# Power_Supply.net
KiCad netlist of a schematic drawn in Altium Designer
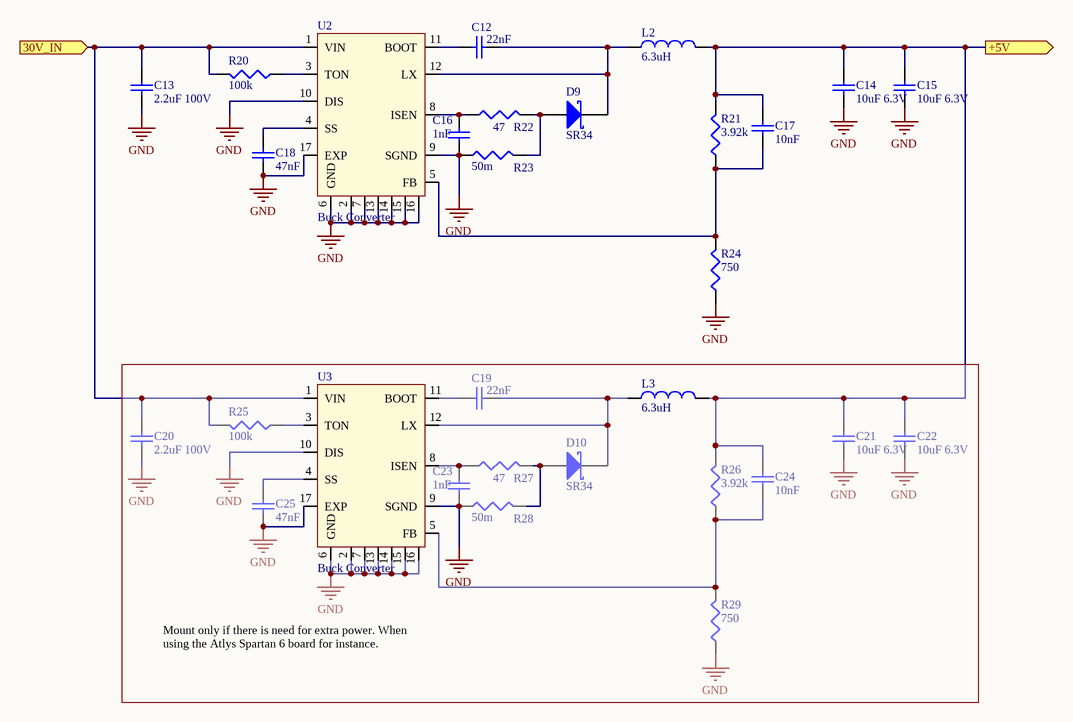
[diagram p0: Power Supply.SchDoc]

(export (version "E")
  (design (tool "Eeschema 10.0.6"))
  (components
    (comp (ref "C12")
      (value "22nF")
      (footprint "6-0805_N")
      (description "Capacitor (Semiconductor SIM Model)")
      (fields (field (name "Comment") "Cap Semi") (field (name "PUBLISHER") "Altium Limited"))
      (libsource (lib "Miscellaneous Devices") (part "Cap Semi"))
    )
    (comp (ref "C13")
      (value "2.2uF 100V")
      (footprint "C1210")
      (description "Capacitor (Semiconductor SIM Model)")
      (fields (field (name "Comment") "Cap Semi") (field (name "PUBLISHER") "Altium Limited"))
      (libsource (lib "Miscellaneous Devices") (part "Cap Semi"))
    )
    (comp (ref "C14")
      (value "10uF 6.3V")
      (footprint "6-0805_N")
      (description "Capacitor (Semiconductor SIM Model)")
      (fields (field (name "Comment") "Cap Semi") (field (name "PUBLISHER") "Altium Limited"))
      (libsource (lib "Miscellaneous Devices") (part "Cap Semi"))
    )
    (comp (ref "C15")
      (value "10uF 6.3V")
      (footprint "6-0805_N")
      (description "Capacitor (Semiconductor SIM Model)")
      (fields (field (name "Comment") "Cap Semi") (field (name "PUBLISHER") "Altium Limited"))
      (libsource (lib "Miscellaneous Devices") (part "Cap Semi"))
    )
    (comp (ref "C16")
      (value "1nF")
      (footprint "6-0805_N")
      (description "Capacitor (Semiconductor SIM Model)")
      (fields (field (name "Comment") "Cap Semi") (field (name "PUBLISHER") "Altium Limited"))
      (libsource (lib "Miscellaneous Devices") (part "Cap Semi"))
    )
    (comp (ref "C17")
      (value "10nF")
      (footprint "6-0805_N")
      (description "Capacitor (Semiconductor SIM Model)")
      (fields (field (name "Comment") "Cap Semi") (field (name "PUBLISHER") "Altium Limited"))
      (libsource (lib "Miscellaneous Devices") (part "Cap Semi"))
    )
    (comp (ref "C18")
      (value "47nF")
      (footprint "6-0805_N")
      (description "Capacitor (Semiconductor SIM Model)")
      (fields (field (name "Comment") "Cap Semi") (field (name "PUBLISHER") "Altium Limited"))
      (libsource (lib "Miscellaneous Devices") (part "Cap Semi"))
    )
    (comp (ref "C19")
      (value "22nF")
      (footprint "6-0805_N")
      (description "Capacitor (Semiconductor SIM Model)")
      (fields (field (name "Comment") "Cap Semi") (field (name "PUBLISHER") "Altium Limited"))
      (libsource (lib "Miscellaneous Devices") (part "Cap Semi"))
    )
    (comp (ref "C20")
      (value "2.2uF 100V")
      (footprint "C1210")
      (description "Capacitor (Semiconductor SIM Model)")
      (fields (field (name "Comment") "Cap Semi") (field (name "PUBLISHER") "Altium Limited"))
      (libsource (lib "Miscellaneous Devices") (part "Cap Semi"))
    )
    (comp (ref "C21")
      (value "10uF 6.3V")
      (footprint "6-0805_N")
      (description "Capacitor (Semiconductor SIM Model)")
      (fields (field (name "Comment") "Cap Semi") (field (name "PUBLISHER") "Altium Limited"))
      (libsource (lib "Miscellaneous Devices") (part "Cap Semi"))
    )
    (comp (ref "C22")
      (value "10uF 6.3V")
      (footprint "6-0805_N")
      (description "Capacitor (Semiconductor SIM Model)")
      (fields (field (name "Comment") "Cap Semi") (field (name "PUBLISHER") "Altium Limited"))
      (libsource (lib "Miscellaneous Devices") (part "Cap Semi"))
    )
    (comp (ref "C23")
      (value "1nF")
      (footprint "6-0805_N")
      (description "Capacitor (Semiconductor SIM Model)")
      (fields (field (name "Comment") "Cap Semi") (field (name "PUBLISHER") "Altium Limited"))
      (libsource (lib "Miscellaneous Devices") (part "Cap Semi"))
    )
    (comp (ref "C24")
      (value "10nF")
      (footprint "6-0805_N")
      (description "Capacitor (Semiconductor SIM Model)")
      (fields (field (name "Comment") "Cap Semi") (field (name "PUBLISHER") "Altium Limited"))
      (libsource (lib "Miscellaneous Devices") (part "Cap Semi"))
    )
    (comp (ref "C25")
      (value "47nF")
      (footprint "6-0805_N")
      (description "Capacitor (Semiconductor SIM Model)")
      (fields (field (name "Comment") "Cap Semi") (field (name "PUBLISHER") "Altium Limited"))
      (libsource (lib "Miscellaneous Devices") (part "Cap Semi"))
    )
    (comp (ref "D9")
      (value "SR34")
      (footprint "CD4532-1812")
      (description "Schottky Diode")
      (fields (field (name "PUBLISHER") "Altium Limited"))
      (libsource (lib "Miscellaneous Devices") (part "D Schottky"))
    )
    (comp (ref "D10")
      (value "SR34")
      (footprint "CD4532-1812")
      (description "Schottky Diode")
      (fields (field (name "PUBLISHER") "Altium Limited"))
      (libsource (lib "Miscellaneous Devices") (part "D Schottky"))
    )
    (comp (ref "L2")
      (value "6.3uH")
      (footprint "WE_74477006")
      (description "Header, 3-Pin")
      (fields (field (name "PUBLISHER") "Altium Limited"))
      (libsource (lib "new_library") (part "Inductor"))
    )
    (comp (ref "L3")
      (value "6.3uH")
      (footprint "WE_74477006")
      (description "Header, 3-Pin")
      (fields (field (name "PUBLISHER") "Altium Limited"))
      (libsource (lib "new_library") (part "Inductor"))
    )
    (comp (ref "R20")
      (value "100k")
      (footprint "6-0805_L")
      (description "Resistor")
      (fields (field (name "Comment") "Res3") (field (name "PUBLISHER") "Altium Limited"))
      (libsource (lib "Miscellaneous Devices") (part "Res3"))
    )
    (comp (ref "R21")
      (value "3.92k")
      (footprint "6-0805_L")
      (description "Resistor")
      (fields (field (name "Comment") "Res3") (field (name "PUBLISHER") "Altium Limited"))
      (libsource (lib "Miscellaneous Devices") (part "Res3"))
    )
    (comp (ref "R22")
      (value "47")
      (footprint "6-0805_L")
      (description "Resistor")
      (fields (field (name "Comment") "Res3") (field (name "PUBLISHER") "Altium Limited"))
      (libsource (lib "Miscellaneous Devices") (part "Res3"))
    )
    (comp (ref "R23")
      (value "50m")
      (footprint "6-0805_L")
      (description "Resistor")
      (fields (field (name "Comment") "Res3") (field (name "PUBLISHER") "Altium Limited"))
      (libsource (lib "Miscellaneous Devices") (part "Res3"))
    )
    (comp (ref "R24")
      (value "750")
      (footprint "6-0805_L")
      (description "Resistor")
      (fields (field (name "Comment") "Res3") (field (name "PUBLISHER") "Altium Limited"))
      (libsource (lib "Miscellaneous Devices") (part "Res3"))
    )
    (comp (ref "R25")
      (value "100k")
      (footprint "6-0805_L")
      (description "Resistor")
      (fields (field (name "Comment") "Res3") (field (name "PUBLISHER") "Altium Limited"))
      (libsource (lib "Miscellaneous Devices") (part "Res3"))
    )
    (comp (ref "R26")
      (value "3.92k")
      (footprint "6-0805_L")
      (description "Resistor")
      (fields (field (name "Comment") "Res3") (field (name "PUBLISHER") "Altium Limited"))
      (libsource (lib "Miscellaneous Devices") (part "Res3"))
    )
    (comp (ref "R27")
      (value "47")
      (footprint "6-0805_L")
      (description "Resistor")
      (fields (field (name "Comment") "Res3") (field (name "PUBLISHER") "Altium Limited"))
      (libsource (lib "Miscellaneous Devices") (part "Res3"))
    )
    (comp (ref "R28")
      (value "50m")
      (footprint "6-0805_L")
      (description "Resistor")
      (fields (field (name "Comment") "Res3") (field (name "PUBLISHER") "Altium Limited"))
      (libsource (lib "Miscellaneous Devices") (part "Res3"))
    )
    (comp (ref "R29")
      (value "750")
      (footprint "6-0805_L")
      (description "Resistor")
      (fields (field (name "Comment") "Res3") (field (name "PUBLISHER") "Altium Limited"))
      (libsource (lib "Miscellaneous Devices") (part "Res3"))
    )
    (comp (ref "U2")
      (value "Buck Converter")
      (footprint "QFN65P400X400X80-16N")
      (description "Header, 3-Pin")
      (fields (field (name "PUBLISHER") "Altium Limited"))
      (libsource (lib "new_library") (part "A4403 Buck Converter"))
    )
    (comp (ref "U3")
      (value "Buck Converter")
      (footprint "QFN65P400X400X80-16N")
      (description "Header, 3-Pin")
      (fields (field (name "PUBLISHER") "Altium Limited"))
      (libsource (lib "new_library") (part "A4403 Buck Converter"))
    )
  )
  (nets
    (net (code "1") (name "/+5V") (class "Default")
      (node (ref "C14") (pin "2") (pinfunction "2_2") (pintype "passive"))
      (node (ref "C15") (pin "2") (pinfunction "2_2") (pintype "passive"))
      (node (ref "C17") (pin "2") (pinfunction "2_2") (pintype "passive"))
      (node (ref "C21") (pin "2") (pinfunction "2_2") (pintype "passive"))
      (node (ref "C22") (pin "2") (pinfunction "2_2") (pintype "passive"))
      (node (ref "C24") (pin "2") (pinfunction "2_2") (pintype "passive"))
      (node (ref "L2") (pin "2") (pinfunction "2_2") (pintype "passive"))
      (node (ref "L3") (pin "2") (pinfunction "2_2") (pintype "passive"))
      (node (ref "R21") (pin "2") (pinfunction "2_2") (pintype "passive"))
      (node (ref "R26") (pin "2") (pinfunction "2_2") (pintype "passive"))
    )
    (net (code "2") (name "/30V_IN") (class "Default")
      (node (ref "C13") (pin "2") (pinfunction "2_2") (pintype "passive"))
      (node (ref "C20") (pin "2") (pinfunction "2_2") (pintype "passive"))
      (node (ref "R20") (pin "2") (pinfunction "2_2") (pintype "passive"))
      (node (ref "R25") (pin "2") (pinfunction "2_2") (pintype "passive"))
      (node (ref "U2") (pin "1") (pinfunction "VIN_1") (pintype "passive"))
      (node (ref "U3") (pin "1") (pinfunction "VIN_1") (pintype "passive"))
    )
    (net (code "3") (name "GND") (class "Default")
      (node (ref "C13") (pin "1") (pinfunction "1_1") (pintype "passive"))
      (node (ref "C14") (pin "1") (pinfunction "1_1") (pintype "passive"))
      (node (ref "C15") (pin "1") (pinfunction "1_1") (pintype "passive"))
      (node (ref "C16") (pin "1") (pinfunction "1_1") (pintype "passive"))
      (node (ref "C18") (pin "1") (pinfunction "1_1") (pintype "passive"))
      (node (ref "C20") (pin "1") (pinfunction "1_1") (pintype "passive"))
      (node (ref "C21") (pin "1") (pinfunction "1_1") (pintype "passive"))
      (node (ref "C22") (pin "1") (pinfunction "1_1") (pintype "passive"))
      (node (ref "C23") (pin "1") (pinfunction "1_1") (pintype "passive"))
      (node (ref "C25") (pin "1") (pinfunction "1_1") (pintype "passive"))
      (node (ref "R23") (pin "1") (pinfunction "1_1") (pintype "passive"))
      (node (ref "R24") (pin "1") (pinfunction "1_1") (pintype "passive"))
      (node (ref "R28") (pin "1") (pinfunction "1_1") (pintype "passive"))
      (node (ref "R29") (pin "1") (pinfunction "1_1") (pintype "passive"))
      (node (ref "U2") (pin "10") (pinfunction "DIS_10") (pintype "passive"))
      (node (ref "U2") (pin "13") (pinfunction "13_13") (pintype "passive"))
      (node (ref "U2") (pin "14") (pinfunction "14_14") (pintype "passive"))
      (node (ref "U2") (pin "15") (pinfunction "15_15") (pintype "passive"))
      (node (ref "U2") (pin "16") (pinfunction "16_16") (pintype "passive"))
      (node (ref "U2") (pin "17") (pinfunction "EXP_17") (pintype "passive"))
      (node (ref "U2") (pin "2") (pinfunction "2_2") (pintype "passive"))
      (node (ref "U2") (pin "6") (pinfunction "GND_6") (pintype "passive"))
      (node (ref "U2") (pin "7") (pinfunction "7_7") (pintype "passive"))
      (node (ref "U2") (pin "9") (pinfunction "SGND_9") (pintype "passive"))
      (node (ref "U3") (pin "10") (pinfunction "DIS_10") (pintype "passive"))
      (node (ref "U3") (pin "13") (pinfunction "13_13") (pintype "passive"))
      (node (ref "U3") (pin "14") (pinfunction "14_14") (pintype "passive"))
      (node (ref "U3") (pin "15") (pinfunction "15_15") (pintype "passive"))
      (node (ref "U3") (pin "16") (pinfunction "16_16") (pintype "passive"))
      (node (ref "U3") (pin "17") (pinfunction "EXP_17") (pintype "passive"))
      (node (ref "U3") (pin "2") (pinfunction "2_2") (pintype "passive"))
      (node (ref "U3") (pin "6") (pinfunction "GND_6") (pintype "passive"))
      (node (ref "U3") (pin "7") (pinfunction "7_7") (pintype "passive"))
      (node (ref "U3") (pin "9") (pinfunction "SGND_9") (pintype "passive"))
    )
    (net (code "4") (name "Net-(D9-A)") (class "Default")
      (node (ref "D9") (pin "1") (pinfunction "A_1") (pintype "passive"))
      (node (ref "R22") (pin "2") (pinfunction "2_2") (pintype "passive"))
      (node (ref "R23") (pin "2") (pinfunction "2_2") (pintype "passive"))
    )
    (net (code "5") (name "Net-(D9-K)") (class "Default")
      (node (ref "C12") (pin "1") (pinfunction "1_1") (pintype "passive"))
      (node (ref "D9") (pin "2") (pinfunction "K_2") (pintype "passive"))
      (node (ref "L2") (pin "1") (pinfunction "1_1") (pintype "passive"))
      (node (ref "U2") (pin "12") (pinfunction "LX_12") (pintype "passive"))
    )
    (net (code "6") (name "Net-(D10-A)") (class "Default")
      (node (ref "D10") (pin "1") (pinfunction "A_1") (pintype "passive"))
      (node (ref "R27") (pin "2") (pinfunction "2_2") (pintype "passive"))
      (node (ref "R28") (pin "2") (pinfunction "2_2") (pintype "passive"))
    )
    (net (code "7") (name "Net-(D10-K)") (class "Default")
      (node (ref "C19") (pin "1") (pinfunction "1_1") (pintype "passive"))
      (node (ref "D10") (pin "2") (pinfunction "K_2") (pintype "passive"))
      (node (ref "L3") (pin "1") (pinfunction "1_1") (pintype "passive"))
      (node (ref "U3") (pin "12") (pinfunction "LX_12") (pintype "passive"))
    )
    (net (code "8") (name "Net-(U2-BOOT)") (class "Default")
      (node (ref "C12") (pin "2") (pinfunction "2_2") (pintype "passive"))
      (node (ref "U2") (pin "11") (pinfunction "BOOT_11") (pintype "passive"))
    )
    (net (code "9") (name "Net-(U2-FB)") (class "Default")
      (node (ref "C17") (pin "1") (pinfunction "1_1") (pintype "passive"))
      (node (ref "R21") (pin "1") (pinfunction "1_1") (pintype "passive"))
      (node (ref "R24") (pin "2") (pinfunction "2_2") (pintype "passive"))
      (node (ref "U2") (pin "5") (pinfunction "FB_5") (pintype "passive"))
    )
    (net (code "10") (name "Net-(U2-ISEN)") (class "Default")
      (node (ref "C16") (pin "2") (pinfunction "2_2") (pintype "passive"))
      (node (ref "R22") (pin "1") (pinfunction "1_1") (pintype "passive"))
      (node (ref "U2") (pin "8") (pinfunction "ISEN_8") (pintype "passive"))
    )
    (net (code "11") (name "Net-(U2-SS)") (class "Default")
      (node (ref "C18") (pin "2") (pinfunction "2_2") (pintype "passive"))
      (node (ref "U2") (pin "4") (pinfunction "SS_4") (pintype "passive"))
    )
    (net (code "12") (name "Net-(U2-TON)") (class "Default")
      (node (ref "R20") (pin "1") (pinfunction "1_1") (pintype "passive"))
      (node (ref "U2") (pin "3") (pinfunction "TON_3") (pintype "passive"))
    )
    (net (code "13") (name "Net-(U3-BOOT)") (class "Default")
      (node (ref "C19") (pin "2") (pinfunction "2_2") (pintype "passive"))
      (node (ref "U3") (pin "11") (pinfunction "BOOT_11") (pintype "passive"))
    )
    (net (code "14") (name "Net-(U3-FB)") (class "Default")
      (node (ref "C24") (pin "1") (pinfunction "1_1") (pintype "passive"))
      (node (ref "R26") (pin "1") (pinfunction "1_1") (pintype "passive"))
      (node (ref "R29") (pin "2") (pinfunction "2_2") (pintype "passive"))
      (node (ref "U3") (pin "5") (pinfunction "FB_5") (pintype "passive"))
    )
    (net (code "15") (name "Net-(U3-ISEN)") (class "Default")
      (node (ref "C23") (pin "2") (pinfunction "2_2") (pintype "passive"))
      (node (ref "R27") (pin "1") (pinfunction "1_1") (pintype "passive"))
      (node (ref "U3") (pin "8") (pinfunction "ISEN_8") (pintype "passive"))
    )
    (net (code "16") (name "Net-(U3-SS)") (class "Default")
      (node (ref "C25") (pin "2") (pinfunction "2_2") (pintype "passive"))
      (node (ref "U3") (pin "4") (pinfunction "SS_4") (pintype "passive"))
    )
    (net (code "17") (name "Net-(U3-TON)") (class "Default")
      (node (ref "R25") (pin "1") (pinfunction "1_1") (pintype "passive"))
      (node (ref "U3") (pin "3") (pinfunction "TON_3") (pintype "passive"))
    )
  )
)
